# mSD-Shield_v11.net
KiCad netlist of a schematic drawn in EAGLE
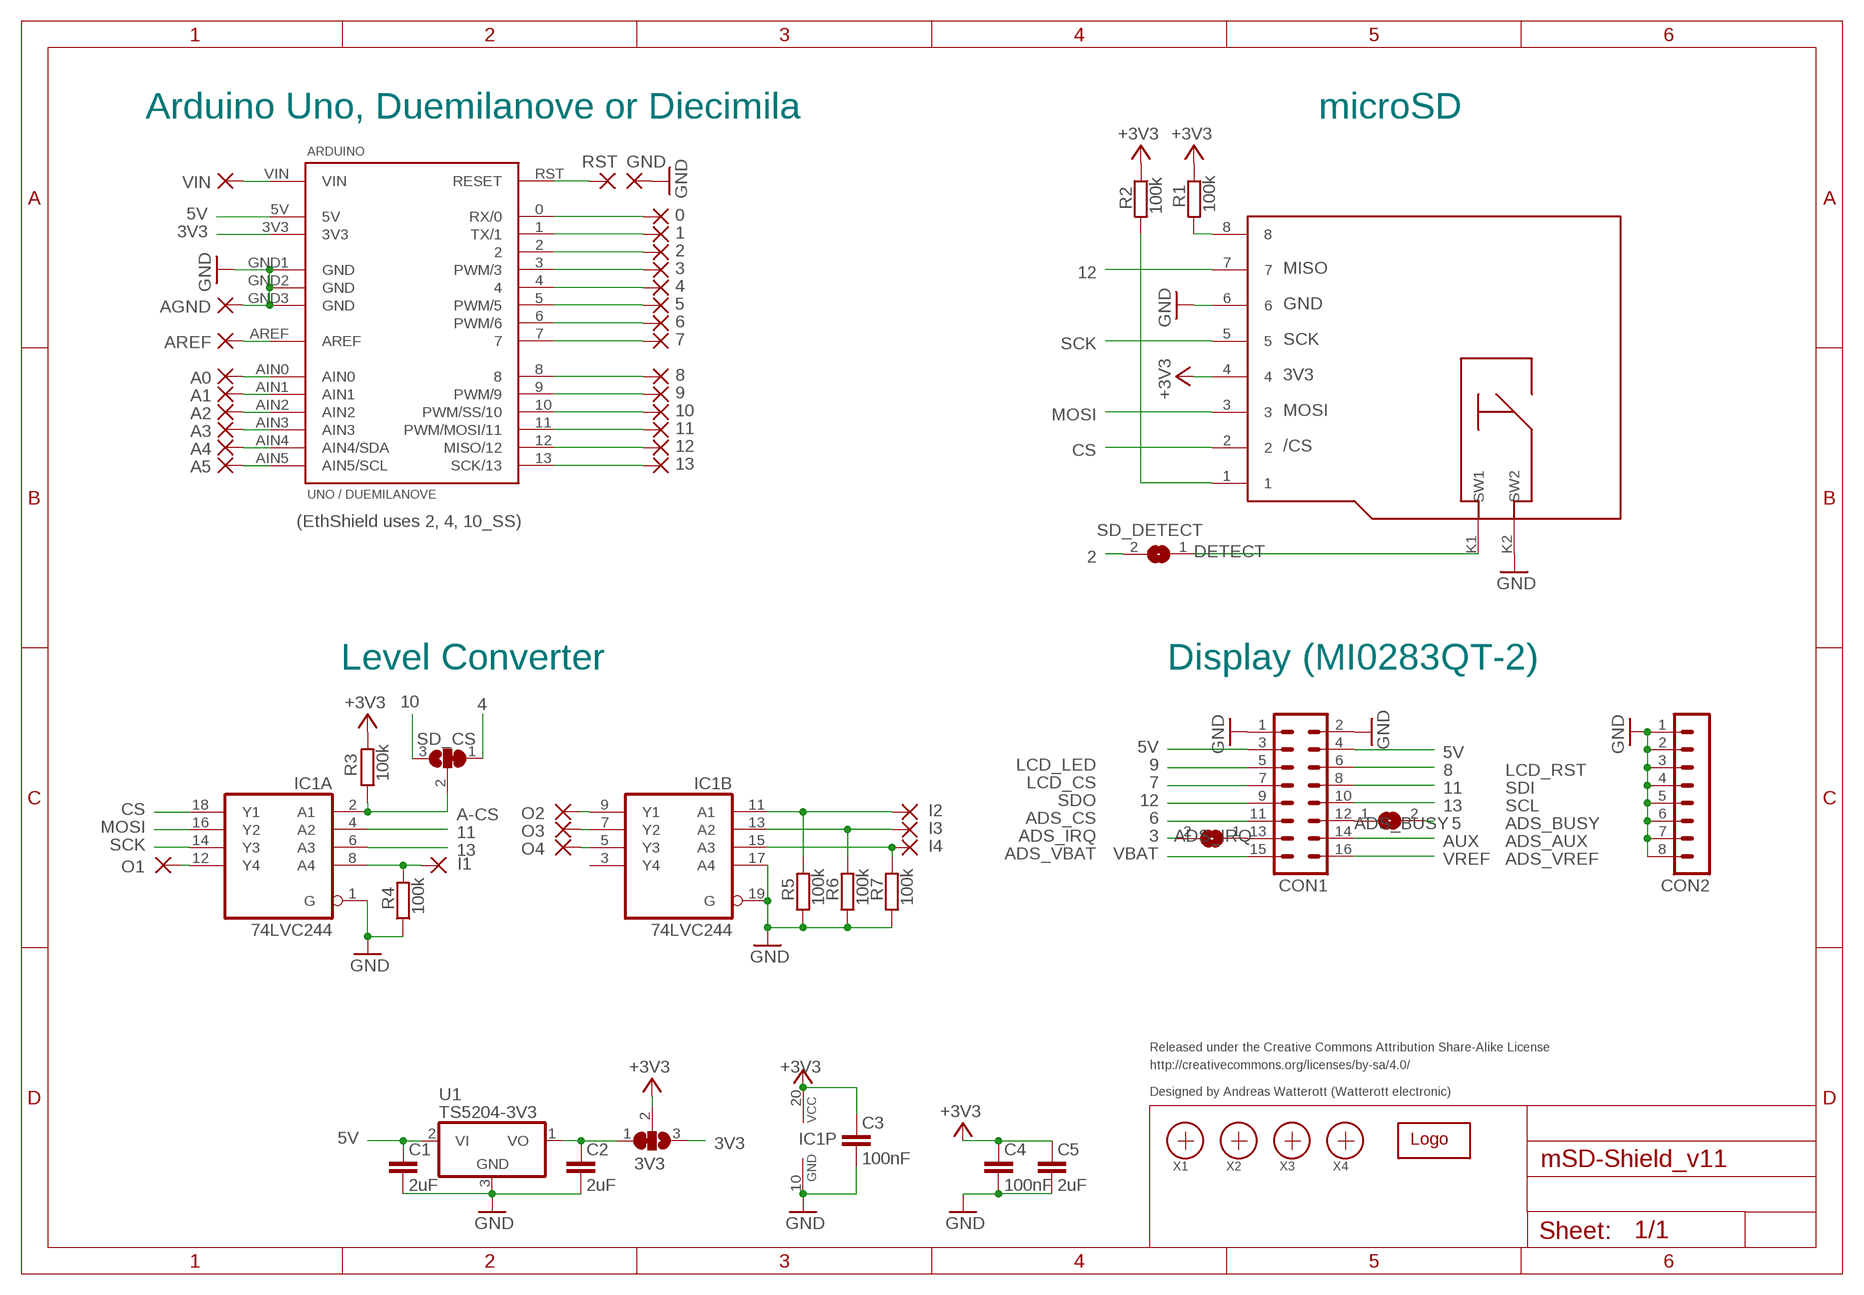
[diagram p0: schematic, sheet 1]

(export (version "E")
  (design (tool "Eeschema 10.0.6"))
  (components
    (comp (ref "0")
      (value "1,6/0,8")
      (footprint "eagle-import:1,6_0,8")
      (libsource (lib "eagle-import") (part "1,6/0,8"))
    )
    (comp (ref "1")
      (value "1,6/0,8")
      (footprint "eagle-import:1,6_0,8")
      (libsource (lib "eagle-import") (part "1,6/0,8"))
    )
    (comp (ref "2")
      (value "1,6/0,8")
      (footprint "eagle-import:1,6_0,8")
      (libsource (lib "eagle-import") (part "1,6/0,8"))
    )
    (comp (ref "3")
      (value "1,6/0,8")
      (footprint "eagle-import:1,6_0,8")
      (libsource (lib "eagle-import") (part "1,6/0,8"))
    )
    (comp (ref "3V3")
      (value "SJ2W")
      (footprint "eagle-import:SJ_2")
      (libsource (lib "eagle-import") (part "SJ2W"))
    )
    (comp (ref "4")
      (value "1,6/0,8")
      (footprint "eagle-import:1,6_0,8")
      (libsource (lib "eagle-import") (part "1,6/0,8"))
    )
    (comp (ref "5")
      (value "1,6/0,8")
      (footprint "eagle-import:1,6_0,8")
      (libsource (lib "eagle-import") (part "1,6/0,8"))
    )
    (comp (ref "6")
      (value "1,6/0,8")
      (footprint "eagle-import:1,6_0,8")
      (libsource (lib "eagle-import") (part "1,6/0,8"))
    )
    (comp (ref "7")
      (value "1,6/0,8")
      (footprint "eagle-import:1,6_0,8")
      (libsource (lib "eagle-import") (part "1,6/0,8"))
    )
    (comp (ref "8")
      (value "1,6/0,8")
      (footprint "eagle-import:1,6_0,8")
      (libsource (lib "eagle-import") (part "1,6/0,8"))
    )
    (comp (ref "9")
      (value "1,6/0,8")
      (footprint "eagle-import:1,6_0,8")
      (libsource (lib "eagle-import") (part "1,6/0,8"))
    )
    (comp (ref "10")
      (value "1,6/0,8")
      (footprint "eagle-import:1,6_0,8")
      (libsource (lib "eagle-import") (part "1,6/0,8"))
    )
    (comp (ref "11")
      (value "1,6/0,8")
      (footprint "eagle-import:1,6_0,8")
      (libsource (lib "eagle-import") (part "1,6/0,8"))
    )
    (comp (ref "12")
      (value "1,6/0,8")
      (footprint "eagle-import:1,6_0,8")
      (libsource (lib "eagle-import") (part "1,6/0,8"))
    )
    (comp (ref "13")
      (value "1,6/0,8")
      (footprint "eagle-import:1,6_0,8")
      (libsource (lib "eagle-import") (part "1,6/0,8"))
    )
    (comp (ref "A0")
      (value "1,6/0,8")
      (footprint "eagle-import:1,6_0,8")
      (libsource (lib "eagle-import") (part "1,6/0,8"))
    )
    (comp (ref "A1")
      (value "1,6/0,8")
      (footprint "eagle-import:1,6_0,8")
      (libsource (lib "eagle-import") (part "1,6/0,8"))
    )
    (comp (ref "A2")
      (value "1,6/0,8")
      (footprint "eagle-import:1,6_0,8")
      (libsource (lib "eagle-import") (part "1,6/0,8"))
    )
    (comp (ref "A3")
      (value "1,6/0,8")
      (footprint "eagle-import:1,6_0,8")
      (libsource (lib "eagle-import") (part "1,6/0,8"))
    )
    (comp (ref "A4")
      (value "1,6/0,8")
      (footprint "eagle-import:1,6_0,8")
      (libsource (lib "eagle-import") (part "1,6/0,8"))
    )
    (comp (ref "A5")
      (value "1,6/0,8")
      (footprint "eagle-import:1,6_0,8")
      (libsource (lib "eagle-import") (part "1,6/0,8"))
    )
    (comp (ref "ADS_BUSY")
      (value "SJ")
      (footprint "eagle-import:SJ")
      (libsource (lib "eagle-import") (part "SJ"))
    )
    (comp (ref "ADS_IRQ")
      (value "SJ")
      (footprint "eagle-import:SJ")
      (libsource (lib "eagle-import") (part "SJ"))
    )
    (comp (ref "AGND")
      (value "1,6/0,8")
      (footprint "eagle-import:1,6_0,8")
      (libsource (lib "eagle-import") (part "1,6/0,8"))
    )
    (comp (ref "ARDUINO")
      (value "UNO / DUEMILANOVE")
      (footprint "eagle-import:DUEMILANOVE2")
      (libsource (lib "eagle-import") (part "DUEMILANOVE2"))
    )
    (comp (ref "AREF")
      (value "1,6/0,8")
      (footprint "eagle-import:1,6_0,8")
      (libsource (lib "eagle-import") (part "1,6/0,8"))
    )
    (comp (ref "C1")
      (value "2uF")
      (footprint "eagle-import:C0805")
      (libsource (lib "eagle-import") (part "C-EUC0805"))
    )
    (comp (ref "C2")
      (value "2uF")
      (footprint "eagle-import:C0805")
      (libsource (lib "eagle-import") (part "C-EUC0805"))
    )
    (comp (ref "C3")
      (value "100nF")
      (footprint "eagle-import:C0603")
      (libsource (lib "eagle-import") (part "C-EUC0603"))
    )
    (comp (ref "C4")
      (value "100nF")
      (footprint "eagle-import:C0603")
      (libsource (lib "eagle-import") (part "C-EUC0603"))
    )
    (comp (ref "C5")
      (value "2uF")
      (footprint "eagle-import:C0603")
      (libsource (lib "eagle-import") (part "C-EUC0603"))
    )
    (comp (ref "CON1")
      (value "MA08-2")
      (footprint "eagle-import:MA08-2")
      (libsource (lib "eagle-import") (part "MA08-2"))
    )
    (comp (ref "CON2")
      (value "MA08-1")
      (footprint "eagle-import:MA08-1")
      (libsource (lib "eagle-import") (part "MA08-1"))
    )
    (comp (ref "GND")
      (value "SMD2")
      (footprint "eagle-import:SMD1,27-2,54")
      (libsource (lib "eagle-import") (part "SMD2"))
    )
    (comp (ref "I1")
      (value "SMD2")
      (footprint "eagle-import:SMD1,27-2,54")
      (libsource (lib "eagle-import") (part "SMD2"))
    )
    (comp (ref "I2")
      (value "SMD2")
      (footprint "eagle-import:SMD1,27-2,54")
      (libsource (lib "eagle-import") (part "SMD2"))
    )
    (comp (ref "I3")
      (value "SMD2")
      (footprint "eagle-import:SMD1,27-2,54")
      (libsource (lib "eagle-import") (part "SMD2"))
    )
    (comp (ref "I4")
      (value "SMD2")
      (footprint "eagle-import:SMD1,27-2,54")
      (libsource (lib "eagle-import") (part "SMD2"))
    )
    (comp (ref "IC1")
      (value "74LVC244")
      (footprint "eagle-import:SO20W")
      (libsource (lib "eagle-import") (part "74244DWHC"))
    )
    (comp (ref "O1")
      (value "SMD2")
      (footprint "eagle-import:SMD1,27-2,54")
      (libsource (lib "eagle-import") (part "SMD2"))
    )
    (comp (ref "O2")
      (value "SMD2")
      (footprint "eagle-import:SMD1,27-2,54")
      (libsource (lib "eagle-import") (part "SMD2"))
    )
    (comp (ref "O3")
      (value "SMD2")
      (footprint "eagle-import:SMD1,27-2,54")
      (libsource (lib "eagle-import") (part "SMD2"))
    )
    (comp (ref "O4")
      (value "SMD2")
      (footprint "eagle-import:SMD1,27-2,54")
      (libsource (lib "eagle-import") (part "SMD2"))
    )
    (comp (ref "R1")
      (value "100k")
      (footprint "eagle-import:R0603")
      (libsource (lib "eagle-import") (part "R-EU_R0603"))
    )
    (comp (ref "R2")
      (value "100k")
      (footprint "eagle-import:R0603")
      (libsource (lib "eagle-import") (part "R-EU_R0603"))
    )
    (comp (ref "R3")
      (value "100k")
      (footprint "eagle-import:R0603")
      (libsource (lib "eagle-import") (part "R-EU_R0603"))
    )
    (comp (ref "R4")
      (value "100k")
      (footprint "eagle-import:R0603")
      (libsource (lib "eagle-import") (part "R-EU_R0603"))
    )
    (comp (ref "R5")
      (value "100k")
      (footprint "eagle-import:R0603")
      (libsource (lib "eagle-import") (part "R-EU_R0603"))
    )
    (comp (ref "R6")
      (value "100k")
      (footprint "eagle-import:R0603")
      (libsource (lib "eagle-import") (part "R-EU_R0603"))
    )
    (comp (ref "R7")
      (value "100k")
      (footprint "eagle-import:R0603")
      (libsource (lib "eagle-import") (part "R-EU_R0603"))
    )
    (comp (ref "RST")
      (value "SMD2")
      (footprint "eagle-import:SMD1,27-2,54")
      (libsource (lib "eagle-import") (part "SMD2"))
    )
    (comp (ref "SD_CS")
      (value "SJ2W")
      (footprint "eagle-import:SJ_2")
      (libsource (lib "eagle-import") (part "SJ2W"))
    )
    (comp (ref "SD_DETECT")
      (value "SJ")
      (footprint "eagle-import:SJ")
      (libsource (lib "eagle-import") (part "SJ"))
    )
    (comp (ref "U$1")
      (value "WE-LOGO")
      (footprint "eagle-import:WE-LOGO")
      (libsource (lib "eagle-import") (part "WE-LOGO"))
    )
    (comp (ref "U1")
      (value "TS5204-3V3")
      (footprint "eagle-import:SOT23")
      (libsource (lib "eagle-import") (part "TS5204"))
    )
    (comp (ref "VIN")
      (value "1,6/0,8")
      (footprint "eagle-import:1,6_0,8")
      (libsource (lib "eagle-import") (part "1,6/0,8"))
    )
    (comp (ref "X1")
      (value "PASSER")
      (footprint "eagle-import:PASSER")
      (libsource (lib "eagle-import") (part "PASSER"))
    )
    (comp (ref "X2")
      (value "PASSER")
      (footprint "eagle-import:PASSER")
      (libsource (lib "eagle-import") (part "PASSER"))
    )
    (comp (ref "X3")
      (value "PASSER")
      (footprint "eagle-import:PASSER")
      (libsource (lib "eagle-import") (part "PASSER"))
    )
    (comp (ref "X4")
      (value "PASSER")
      (footprint "eagle-import:PASSER")
      (libsource (lib "eagle-import") (part "PASSER"))
    )
    (comp (ref "X5")
      (value "MICRO-SD")
      (footprint "eagle-import:MICRO-SD")
      (libsource (lib "eagle-import") (part "MICRO-SD"))
    )
  )
  (nets
    (net (code "1") (name "+3V3") (class "Default")
      (node (ref "3V3") (pin "2") (pinfunction "2_2") (pintype "passive"))
      (node (ref "C3") (pin "1") (pinfunction "1_1") (pintype "passive"))
      (node (ref "C4") (pin "1") (pinfunction "1_1") (pintype "passive"))
      (node (ref "C5") (pin "1") (pinfunction "1_1") (pintype "passive"))
      (node (ref "IC1") (pin "20") (pinfunction "VCC_20") (pintype "power_in"))
      (node (ref "R1") (pin "1") (pinfunction "1_1") (pintype "passive"))
      (node (ref "R2") (pin "1") (pinfunction "1_1") (pintype "passive"))
      (node (ref "R3") (pin "2") (pinfunction "2_2") (pintype "passive"))
      (node (ref "X5") (pin "4") (pinfunction "4_4") (pintype "bidirectional"))
    )
    (net (code "2") (name "/2") (class "Default")
      (node (ref "2") (pin "1") (pinfunction "P_1") (pintype "passive"))
      (node (ref "ARDUINO") (pin "2") (pinfunction "2_2") (pintype "bidirectional"))
      (node (ref "SD_DETECT") (pin "2") (pinfunction "2_2") (pintype "passive"))
    )
    (net (code "3") (name "/3") (class "Default")
      (node (ref "3") (pin "1") (pinfunction "P_1") (pintype "passive"))
      (node (ref "ADS_IRQ") (pin "2") (pinfunction "2_2") (pintype "passive"))
      (node (ref "ARDUINO") (pin "3") (pinfunction "PWM/3_3") (pintype "bidirectional"))
    )
    (net (code "4") (name "/3V3") (class "Default")
      (node (ref "3V3") (pin "3") (pinfunction "3_3") (pintype "passive"))
      (node (ref "ARDUINO") (pin "3V3") (pinfunction "3V3_3V3") (pintype "power_in"))
    )
    (net (code "5") (name "/4") (class "Default")
      (node (ref "4") (pin "1") (pinfunction "P_1") (pintype "passive"))
      (node (ref "ARDUINO") (pin "4") (pinfunction "4_4") (pintype "bidirectional"))
      (node (ref "SD_CS") (pin "1") (pinfunction "1_1") (pintype "passive"))
    )
    (net (code "6") (name "/5") (class "Default")
      (node (ref "5") (pin "1") (pinfunction "P_1") (pintype "passive"))
      (node (ref "ADS_BUSY") (pin "2") (pinfunction "2_2") (pintype "passive"))
      (node (ref "ARDUINO") (pin "5") (pinfunction "PWM/5_5") (pintype "bidirectional"))
    )
    (net (code "7") (name "/5V") (class "Default")
      (node (ref "ARDUINO") (pin "5V") (pinfunction "5V_5V") (pintype "power_in"))
      (node (ref "C1") (pin "1") (pinfunction "1_1") (pintype "passive"))
      (node (ref "CON1") (pin "3") (pinfunction "3_3") (pintype "passive"))
      (node (ref "CON1") (pin "4") (pinfunction "4_4") (pintype "passive"))
      (node (ref "U1") (pin "2") (pinfunction "VI_2") (pintype "input"))
    )
    (net (code "8") (name "/6") (class "Default")
      (node (ref "6") (pin "1") (pinfunction "P_1") (pintype "passive"))
      (node (ref "ARDUINO") (pin "6") (pinfunction "PWM/6_6") (pintype "bidirectional"))
      (node (ref "CON1") (pin "11") (pinfunction "11_11") (pintype "passive"))
    )
    (net (code "9") (name "/7") (class "Default")
      (node (ref "7") (pin "1") (pinfunction "P_1") (pintype "passive"))
      (node (ref "ARDUINO") (pin "7") (pinfunction "7_7") (pintype "bidirectional"))
      (node (ref "CON1") (pin "7") (pinfunction "7_7") (pintype "passive"))
    )
    (net (code "10") (name "/8") (class "Default")
      (node (ref "8") (pin "1") (pinfunction "P_1") (pintype "passive"))
      (node (ref "ARDUINO") (pin "8") (pinfunction "8_8") (pintype "bidirectional"))
      (node (ref "CON1") (pin "6") (pinfunction "6_6") (pintype "passive"))
    )
    (net (code "11") (name "/9") (class "Default")
      (node (ref "9") (pin "1") (pinfunction "P_1") (pintype "passive"))
      (node (ref "ARDUINO") (pin "9") (pinfunction "PWM/9_9") (pintype "bidirectional"))
      (node (ref "CON1") (pin "5") (pinfunction "5_5") (pintype "passive"))
    )
    (net (code "12") (name "/10") (class "Default")
      (node (ref "10") (pin "1") (pinfunction "P_1") (pintype "passive"))
      (node (ref "ARDUINO") (pin "10") (pinfunction "PWM/SS/10_10") (pintype "bidirectional"))
      (node (ref "SD_CS") (pin "3") (pinfunction "3_3") (pintype "passive"))
    )
    (net (code "13") (name "/11") (class "Default")
      (node (ref "11") (pin "1") (pinfunction "P_1") (pintype "passive"))
      (node (ref "ARDUINO") (pin "11") (pinfunction "PWM/MOSI/11_11") (pintype "bidirectional"))
      (node (ref "CON1") (pin "8") (pinfunction "8_8") (pintype "passive"))
      (node (ref "IC1") (pin "4") (pinfunction "A2_4") (pintype "input"))
    )
    (net (code "14") (name "/12") (class "Default")
      (node (ref "12") (pin "1") (pinfunction "P_1") (pintype "passive"))
      (node (ref "ARDUINO") (pin "12") (pinfunction "MISO/12_12") (pintype "bidirectional"))
      (node (ref "CON1") (pin "9") (pinfunction "9_9") (pintype "passive"))
      (node (ref "X5") (pin "7") (pinfunction "7_7") (pintype "bidirectional"))
    )
    (net (code "15") (name "/13") (class "Default")
      (node (ref "13") (pin "1") (pinfunction "P_1") (pintype "passive"))
      (node (ref "ARDUINO") (pin "13") (pinfunction "SCK/13_13") (pintype "bidirectional"))
      (node (ref "CON1") (pin "10") (pinfunction "10_10") (pintype "passive"))
      (node (ref "IC1") (pin "6") (pinfunction "A3_6") (pintype "input"))
    )
    (net (code "16") (name "/A-CS") (class "Default")
      (node (ref "IC1") (pin "2") (pinfunction "A1_2") (pintype "input"))
      (node (ref "R3") (pin "1") (pinfunction "1_1") (pintype "passive"))
      (node (ref "SD_CS") (pin "2") (pinfunction "2_2") (pintype "passive"))
    )
    (net (code "17") (name "/AUX") (class "Default")
      (node (ref "CON1") (pin "14") (pinfunction "14_14") (pintype "passive"))
    )
    (net (code "18") (name "/CS") (class "Default")
      (node (ref "IC1") (pin "18") (pinfunction "Y1_18") (pintype "tri_state"))
      (node (ref "X5") (pin "2") (pinfunction "2_2") (pintype "bidirectional"))
    )
    (net (code "19") (name "/DETECT") (class "Default")
      (node (ref "SD_DETECT") (pin "1") (pinfunction "1_1") (pintype "passive"))
      (node (ref "X5") (pin "K1") (pinfunction "SW1_K1") (pintype "bidirectional"))
    )
    (net (code "20") (name "/MOSI") (class "Default")
      (node (ref "IC1") (pin "16") (pinfunction "Y2_16") (pintype "tri_state"))
      (node (ref "X5") (pin "3") (pinfunction "3_3") (pintype "bidirectional"))
    )
    (net (code "21") (name "/SCK") (class "Default")
      (node (ref "IC1") (pin "14") (pinfunction "Y3_14") (pintype "tri_state"))
      (node (ref "X5") (pin "5") (pinfunction "5_5") (pintype "bidirectional"))
    )
    (net (code "22") (name "/VBAT") (class "Default")
      (node (ref "CON1") (pin "15") (pinfunction "15_15") (pintype "passive"))
    )
    (net (code "23") (name "/VREF") (class "Default")
      (node (ref "CON1") (pin "16") (pinfunction "16_16") (pintype "passive"))
    )
    (net (code "24") (name "GND") (class "Default")
      (node (ref "AGND") (pin "1") (pinfunction "P_1") (pintype "passive"))
      (node (ref "ARDUINO") (pin "GND1") (pinfunction "GND_GND1") (pintype "power_in"))
      (node (ref "ARDUINO") (pin "GND2") (pinfunction "GND_GND2") (pintype "power_in"))
      (node (ref "ARDUINO") (pin "GND3") (pinfunction "GND_GND3") (pintype "power_in"))
      (node (ref "C1") (pin "2") (pinfunction "2_2") (pintype "passive"))
      (node (ref "C2") (pin "2") (pinfunction "2_2") (pintype "passive"))
      (node (ref "C3") (pin "2") (pinfunction "2_2") (pintype "passive"))
      (node (ref "C4") (pin "2") (pinfunction "2_2") (pintype "passive"))
      (node (ref "C5") (pin "2") (pinfunction "2_2") (pintype "passive"))
      (node (ref "CON1") (pin "1") (pinfunction "1_1") (pintype "passive"))
      (node (ref "CON1") (pin "2") (pinfunction "2_2") (pintype "passive"))
      (node (ref "CON2") (pin "1") (pinfunction "1_1") (pintype "passive"))
      (node (ref "CON2") (pin "2") (pinfunction "2_2") (pintype "passive"))
      (node (ref "CON2") (pin "3") (pinfunction "3_3") (pintype "passive"))
      (node (ref "CON2") (pin "4") (pinfunction "4_4") (pintype "passive"))
      (node (ref "CON2") (pin "5") (pinfunction "5_5") (pintype "passive"))
      (node (ref "CON2") (pin "6") (pinfunction "6_6") (pintype "passive"))
      (node (ref "CON2") (pin "7") (pinfunction "7_7") (pintype "passive"))
      (node (ref "CON2") (pin "8") (pinfunction "8_8") (pintype "passive"))
      (node (ref "GND") (pin "1") (pinfunction "P_1") (pintype "passive"))
      (node (ref "IC1") (pin "1") (pinfunction "G_1") (pintype "input"))
      (node (ref "IC1") (pin "10") (pinfunction "GND_10") (pintype "power_in"))
      (node (ref "IC1") (pin "17") (pinfunction "A4_17") (pintype "input"))
      (node (ref "IC1") (pin "19") (pinfunction "G_19") (pintype "input"))
      (node (ref "R4") (pin "1") (pinfunction "1_1") (pintype "passive"))
      (node (ref "R5") (pin "1") (pinfunction "1_1") (pintype "passive"))
      (node (ref "R6") (pin "1") (pinfunction "1_1") (pintype "passive"))
      (node (ref "R7") (pin "1") (pinfunction "1_1") (pintype "passive"))
      (node (ref "U1") (pin "3") (pinfunction "GND_3") (pintype "passive"))
      (node (ref "X5") (pin "6") (pinfunction "6_6") (pintype "bidirectional"))
      (node (ref "X5") (pin "K2") (pinfunction "SW2_K2") (pintype "bidirectional"))
    )
    (net (code "25") (name "Net-(0-P)") (class "Default")
      (node (ref "0") (pin "1") (pinfunction "P_1") (pintype "passive"))
      (node (ref "ARDUINO") (pin "0") (pinfunction "RX/0_0") (pintype "bidirectional"))
    )
    (net (code "26") (name "Net-(1-P)") (class "Default")
      (node (ref "1") (pin "1") (pinfunction "P_1") (pintype "passive"))
      (node (ref "ARDUINO") (pin "1") (pinfunction "TX/1_1") (pintype "bidirectional"))
    )
    (net (code "27") (name "Net-(A0-P)") (class "Default")
      (node (ref "A0") (pin "1") (pinfunction "P_1") (pintype "passive"))
      (node (ref "ARDUINO") (pin "AIN0") (pinfunction "AIN0_AIN0") (pintype "bidirectional"))
    )
    (net (code "28") (name "Net-(A1-P)") (class "Default")
      (node (ref "A1") (pin "1") (pinfunction "P_1") (pintype "passive"))
      (node (ref "ARDUINO") (pin "AIN1") (pinfunction "AIN1_AIN1") (pintype "bidirectional"))
    )
    (net (code "29") (name "Net-(A2-P)") (class "Default")
      (node (ref "A2") (pin "1") (pinfunction "P_1") (pintype "passive"))
      (node (ref "ARDUINO") (pin "AIN2") (pinfunction "AIN2_AIN2") (pintype "bidirectional"))
    )
    (net (code "30") (name "Net-(A3-P)") (class "Default")
      (node (ref "A3") (pin "1") (pinfunction "P_1") (pintype "passive"))
      (node (ref "ARDUINO") (pin "AIN3") (pinfunction "AIN3_AIN3") (pintype "bidirectional"))
    )
    (net (code "31") (name "Net-(A4-P)") (class "Default")
      (node (ref "A4") (pin "1") (pinfunction "P_1") (pintype "passive"))
      (node (ref "ARDUINO") (pin "AIN4") (pinfunction "AIN4/SDA_AIN4") (pintype "bidirectional"))
    )
    (net (code "32") (name "Net-(A5-P)") (class "Default")
      (node (ref "A5") (pin "1") (pinfunction "P_1") (pintype "passive"))
      (node (ref "ARDUINO") (pin "AIN5") (pinfunction "AIN5/SCL_AIN5") (pintype "bidirectional"))
    )
    (net (code "33") (name "Net-(ADS_BUSY-Pad1)") (class "Default")
      (node (ref "ADS_BUSY") (pin "1") (pinfunction "1_1") (pintype "passive"))
      (node (ref "CON1") (pin "12") (pinfunction "12_12") (pintype "passive"))
    )
    (net (code "34") (name "Net-(ADS_IRQ-Pad1)") (class "Default")
      (node (ref "ADS_IRQ") (pin "1") (pinfunction "1_1") (pintype "passive"))
      (node (ref "CON1") (pin "13") (pinfunction "13_13") (pintype "passive"))
    )
    (net (code "35") (name "Net-(ARDUINO-RESET)") (class "Default")
      (node (ref "ARDUINO") (pin "RST") (pinfunction "RESET_RST") (pintype "bidirectional"))
      (node (ref "RST") (pin "1") (pinfunction "P_1") (pintype "passive"))
    )
    (net (code "36") (name "Net-(AREF-P)") (class "Default")
      (node (ref "ARDUINO") (pin "AREF") (pinfunction "AREF_AREF") (pintype "power_in"))
      (node (ref "AREF") (pin "1") (pinfunction "P_1") (pintype "passive"))
    )
    (net (code "37") (name "Net-(I1-P)") (class "Default")
      (node (ref "I1") (pin "1") (pinfunction "P_1") (pintype "passive"))
      (node (ref "IC1") (pin "8") (pinfunction "A4_8") (pintype "input"))
      (node (ref "R4") (pin "2") (pinfunction "2_2") (pintype "passive"))
    )
    (net (code "38") (name "Net-(I2-P)") (class "Default")
      (node (ref "I2") (pin "1") (pinfunction "P_1") (pintype "passive"))
      (node (ref "IC1") (pin "11") (pinfunction "A1_11") (pintype "input"))
      (node (ref "R5") (pin "2") (pinfunction "2_2") (pintype "passive"))
    )
    (net (code "39") (name "Net-(I3-P)") (class "Default")
      (node (ref "I3") (pin "1") (pinfunction "P_1") (pintype "passive"))
      (node (ref "IC1") (pin "13") (pinfunction "A2_13") (pintype "input"))
      (node (ref "R6") (pin "2") (pinfunction "2_2") (pintype "passive"))
    )
    (net (code "40") (name "Net-(I4-P)") (class "Default")
      (node (ref "I4") (pin "1") (pinfunction "P_1") (pintype "passive"))
      (node (ref "IC1") (pin "15") (pinfunction "A3_15") (pintype "input"))
      (node (ref "R7") (pin "2") (pinfunction "2_2") (pintype "passive"))
    )
    (net (code "41") (name "Net-(IC1A-Y4)") (class "Default")
      (node (ref "IC1") (pin "12") (pinfunction "Y4_12") (pintype "tri_state"))
      (node (ref "O1") (pin "1") (pinfunction "P_1") (pintype "passive"))
    )
    (net (code "42") (name "Net-(IC1B-Y1)") (class "Default")
      (node (ref "IC1") (pin "9") (pinfunction "Y1_9") (pintype "tri_state"))
      (node (ref "O2") (pin "1") (pinfunction "P_1") (pintype "passive"))
    )
    (net (code "43") (name "Net-(IC1B-Y2)") (class "Default")
      (node (ref "IC1") (pin "7") (pinfunction "Y2_7") (pintype "tri_state"))
      (node (ref "O3") (pin "1") (pinfunction "P_1") (pintype "passive"))
    )
    (net (code "44") (name "Net-(IC1B-Y3)") (class "Default")
      (node (ref "IC1") (pin "5") (pinfunction "Y3_5") (pintype "tri_state"))
      (node (ref "O4") (pin "1") (pinfunction "P_1") (pintype "passive"))
    )
    (net (code "45") (name "Net-(R1-Pad2)") (class "Default")
      (node (ref "R1") (pin "2") (pinfunction "2_2") (pintype "passive"))
      (node (ref "X5") (pin "8") (pinfunction "8_8") (pintype "bidirectional"))
    )
    (net (code "46") (name "Net-(R2-Pad2)") (class "Default")
      (node (ref "R2") (pin "2") (pinfunction "2_2") (pintype "passive"))
      (node (ref "X5") (pin "1") (pinfunction "1_1") (pintype "bidirectional"))
    )
    (net (code "47") (name "Net-(U1-VO)") (class "Default")
      (node (ref "3V3") (pin "1") (pinfunction "1_1") (pintype "passive"))
      (node (ref "C2") (pin "1") (pinfunction "1_1") (pintype "passive"))
      (node (ref "U1") (pin "1") (pinfunction "VO_1") (pintype "passive"))
    )
    (net (code "48") (name "Net-(VIN-P)") (class "Default")
      (node (ref "ARDUINO") (pin "VIN") (pinfunction "VIN_VIN") (pintype "power_in"))
      (node (ref "VIN") (pin "1") (pinfunction "P_1") (pintype "passive"))
    )
    (net (code "49") (name "unconnected-(IC1B-Y4-Pad3)") (class "Default")
      (node (ref "IC1") (pin "3") (pinfunction "Y4_3") (pintype "tri_state"))
    )
  )
)
